# rj45_hub.net
KiCad netlist of a schematic drawn in Altium Designer
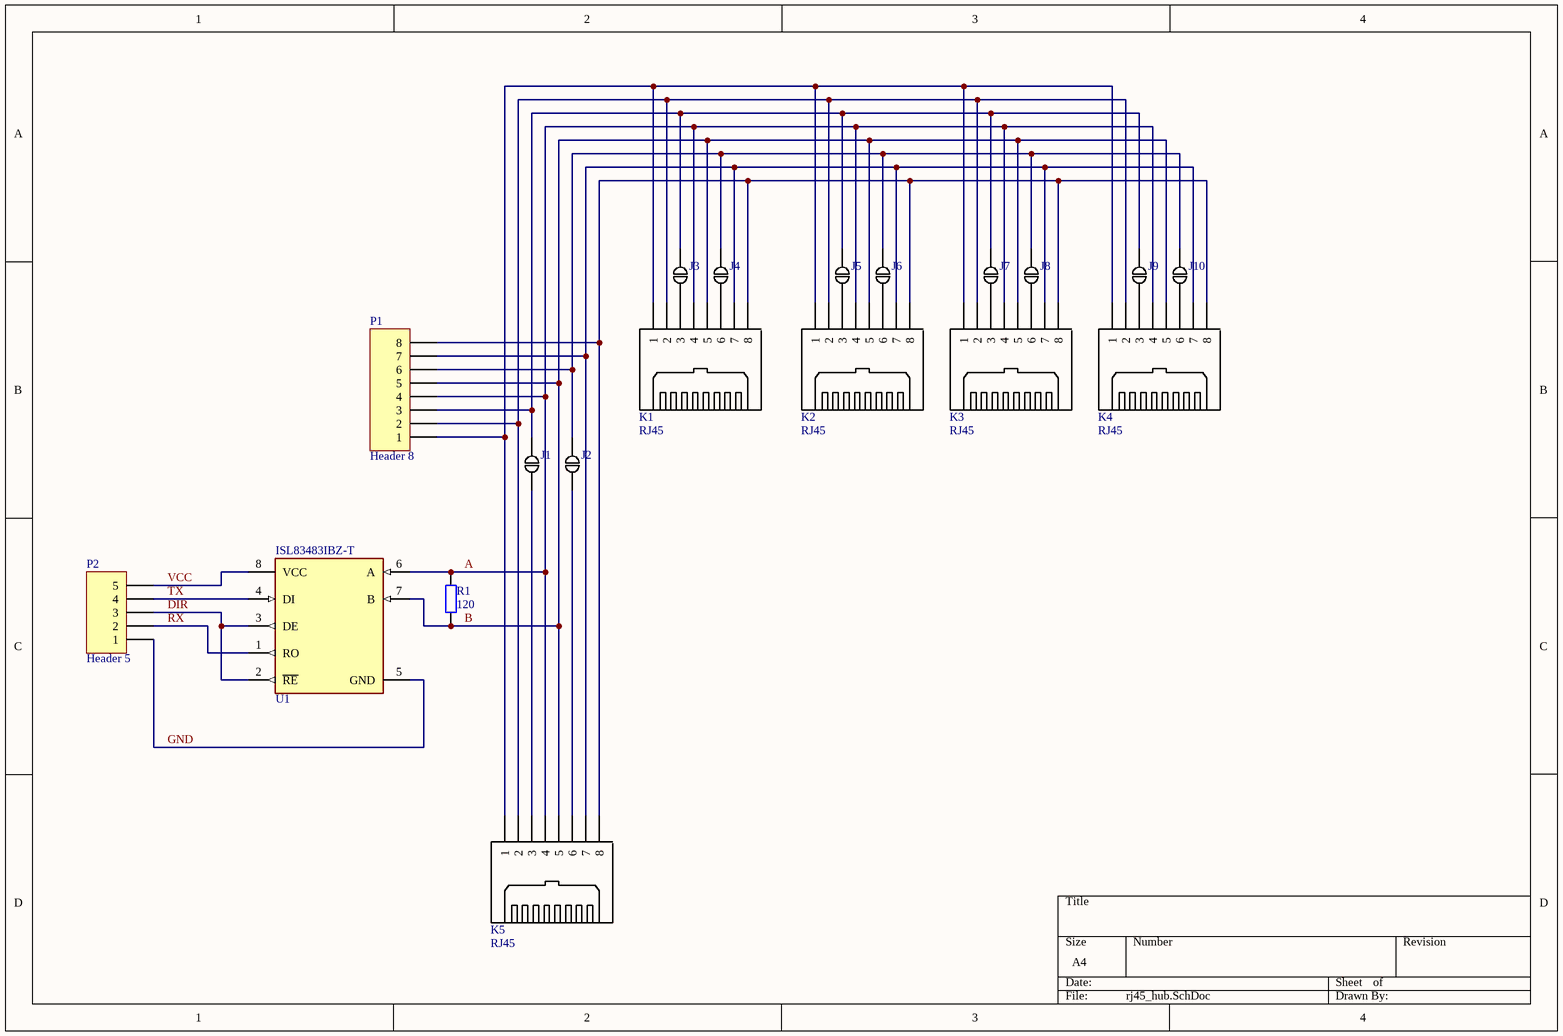
[diagram p0: rj45_hub.SchDoc]

(export (version "E")
  (design (tool "Eeschema 10.0.6"))
  (components
    (comp (ref "J1")
      (value "~")
      (footprint "SOLDER_JUMP")
      (description "SOLDERDOT BYPASS")
      (libsource (lib "vh_altium_library") (part "BYPASS-MINI"))
    )
    (comp (ref "J2")
      (value "~")
      (footprint "SOLDER_JUMP")
      (description "SOLDERDOT BYPASS")
      (libsource (lib "vh_altium_library") (part "BYPASS-MINI"))
    )
    (comp (ref "J3")
      (value "~")
      (footprint "SOLDER_JUMP")
      (description "SOLDERDOT BYPASS")
      (libsource (lib "vh_altium_library") (part "BYPASS-MINI"))
    )
    (comp (ref "J4")
      (value "~")
      (footprint "SOLDER_JUMP")
      (description "SOLDERDOT BYPASS")
      (libsource (lib "vh_altium_library") (part "BYPASS-MINI"))
    )
    (comp (ref "J5")
      (value "~")
      (footprint "SOLDER_JUMP")
      (description "SOLDERDOT BYPASS")
      (libsource (lib "vh_altium_library") (part "BYPASS-MINI"))
    )
    (comp (ref "J6")
      (value "~")
      (footprint "SOLDER_JUMP")
      (description "SOLDERDOT BYPASS")
      (libsource (lib "vh_altium_library") (part "BYPASS-MINI"))
    )
    (comp (ref "J7")
      (value "~")
      (footprint "SOLDER_JUMP")
      (description "SOLDERDOT BYPASS")
      (libsource (lib "vh_altium_library") (part "BYPASS-MINI"))
    )
    (comp (ref "J8")
      (value "~")
      (footprint "SOLDER_JUMP")
      (description "SOLDERDOT BYPASS")
      (libsource (lib "vh_altium_library") (part "BYPASS-MINI"))
    )
    (comp (ref "J9")
      (value "~")
      (footprint "SOLDER_JUMP")
      (description "SOLDERDOT BYPASS")
      (libsource (lib "vh_altium_library") (part "BYPASS-MINI"))
    )
    (comp (ref "J10")
      (value "~")
      (footprint "SOLDER_JUMP")
      (description "SOLDERDOT BYPASS")
      (libsource (lib "vh_altium_library") (part "BYPASS-MINI"))
    )
    (comp (ref "K1") (value "RJ45") (footprint "rj45") (libsource (lib "vh_altium_library") (part "RJ45")))
    (comp (ref "K2") (value "RJ45") (footprint "rj45") (libsource (lib "vh_altium_library") (part "RJ45")))
    (comp (ref "K3") (value "RJ45") (footprint "rj45") (libsource (lib "vh_altium_library") (part "RJ45")))
    (comp (ref "K4") (value "RJ45") (footprint "rj45") (libsource (lib "vh_altium_library") (part "RJ45")))
    (comp (ref "K5") (value "RJ45") (footprint "rj45") (libsource (lib "vh_altium_library") (part "RJ45")))
    (comp (ref "P1")
      (value "Header 8")
      (footprint "HDR1X8")
      (description "Header, 8-Pin")
      (fields (field (name "PUBLISHER") "Altium Limited"))
      (libsource (lib "Miscellaneous Connectors") (part "Header 8"))
    )
    (comp (ref "P2")
      (value "Header 5")
      (footprint "HDR1X5")
      (description "Header, 5-Pin")
      (fields (field (name "PUBLISHER") "Altium Limited"))
      (libsource (lib "Miscellaneous Connectors") (part "Header 5"))
    )
    (comp (ref "R1")
      (value "120")
      (footprint "0603R-GENERIC")
      (description "Resistor")
      (fields (field (name "Comment") "Res2") (field (name "PUBLISHER") "Altium Limited"))
      (libsource (lib "Miscellaneous Devices") (part "Res2"))
    )
    (comp (ref "U1")
      (value "ISL83483IBZ-T")
      (footprint "FP-S8-5-MFG")
      (description "IC TRANSCEIVER HALF 1/1 8SOIC")
      (fields
        (field (name "MANUFACTURER PART NUMBER") "MAX483ECSA+")
        (field (name "OCTOPART") "https://octopart.com/max483ecsa%2B-maxim+integrated-39583309")
      )
      (libsource (lib "Altium Content Vault") (part "CMP-05679-000034-1"))
    )
  )
  (nets
    (net (code "1") (name "/A") (class "Default")
      (node (ref "K1") (pin "4") (pinfunction "4_4") (pintype "passive"))
      (node (ref "K2") (pin "4") (pinfunction "4_4") (pintype "passive"))
      (node (ref "K3") (pin "4") (pinfunction "4_4") (pintype "passive"))
      (node (ref "K4") (pin "4") (pinfunction "4_4") (pintype "passive"))
      (node (ref "K5") (pin "4") (pinfunction "4_4") (pintype "passive"))
      (node (ref "P1") (pin "4") (pinfunction "4_4") (pintype "passive"))
      (node (ref "R1") (pin "2") (pinfunction "2_2") (pintype "passive"))
      (node (ref "U1") (pin "6") (pinfunction "A_6") (pintype "input"))
    )
    (net (code "2") (name "/B") (class "Default")
      (node (ref "K1") (pin "5") (pinfunction "5_5") (pintype "passive"))
      (node (ref "K2") (pin "5") (pinfunction "5_5") (pintype "passive"))
      (node (ref "K3") (pin "5") (pinfunction "5_5") (pintype "passive"))
      (node (ref "K4") (pin "5") (pinfunction "5_5") (pintype "passive"))
      (node (ref "K5") (pin "5") (pinfunction "5_5") (pintype "passive"))
      (node (ref "P1") (pin "5") (pinfunction "5_5") (pintype "passive"))
      (node (ref "R1") (pin "1") (pinfunction "1_1") (pintype "passive"))
      (node (ref "U1") (pin "7") (pinfunction "B_7") (pintype "input"))
    )
    (net (code "3") (name "/DIR") (class "Default")
      (node (ref "P2") (pin "3") (pinfunction "3_3") (pintype "passive"))
      (node (ref "U1") (pin "2") (pinfunction "~{RE}_2") (pintype "output"))
      (node (ref "U1") (pin "3") (pinfunction "DE_3") (pintype "output"))
    )
    (net (code "4") (name "/GND") (class "Default")
      (node (ref "P2") (pin "1") (pinfunction "1_1") (pintype "passive"))
      (node (ref "U1") (pin "5") (pinfunction "GND_5") (pintype "power_in"))
    )
    (net (code "5") (name "/RX") (class "Default")
      (node (ref "P2") (pin "2") (pinfunction "2_2") (pintype "passive"))
      (node (ref "U1") (pin "1") (pinfunction "RO_1") (pintype "output"))
    )
    (net (code "6") (name "/TX") (class "Default")
      (node (ref "P2") (pin "4") (pinfunction "4_4") (pintype "passive"))
      (node (ref "U1") (pin "4") (pinfunction "DI_4") (pintype "input"))
    )
    (net (code "7") (name "/VCC") (class "Default")
      (node (ref "P2") (pin "5") (pinfunction "5_5") (pintype "passive"))
      (node (ref "U1") (pin "8") (pinfunction "VCC_8") (pintype "power_in"))
    )
    (net (code "8") (name "Net-(J1-Pad1)") (class "Default")
      (node (ref "J1") (pin "1") (pinfunction "1_1") (pintype "passive"))
      (node (ref "J3") (pin "1") (pinfunction "1_1") (pintype "passive"))
      (node (ref "J5") (pin "1") (pinfunction "1_1") (pintype "passive"))
      (node (ref "J7") (pin "1") (pinfunction "1_1") (pintype "passive"))
      (node (ref "J9") (pin "1") (pinfunction "1_1") (pintype "passive"))
      (node (ref "P1") (pin "3") (pinfunction "3_3") (pintype "passive"))
    )
    (net (code "9") (name "Net-(J1-Pad2)") (class "Default")
      (node (ref "J1") (pin "2") (pinfunction "2_2") (pintype "passive"))
      (node (ref "K5") (pin "3") (pinfunction "3_3") (pintype "passive"))
    )
    (net (code "10") (name "Net-(J2-Pad2)") (class "Default")
      (node (ref "J2") (pin "2") (pinfunction "2_2") (pintype "passive"))
      (node (ref "K5") (pin "6") (pinfunction "6_6") (pintype "passive"))
    )
    (net (code "11") (name "Net-(J3-Pad2)") (class "Default")
      (node (ref "J3") (pin "2") (pinfunction "2_2") (pintype "passive"))
      (node (ref "K1") (pin "3") (pinfunction "3_3") (pintype "passive"))
    )
    (net (code "12") (name "Net-(J4-Pad2)") (class "Default")
      (node (ref "J4") (pin "2") (pinfunction "2_2") (pintype "passive"))
      (node (ref "K1") (pin "6") (pinfunction "6_6") (pintype "passive"))
    )
    (net (code "13") (name "Net-(J5-Pad2)") (class "Default")
      (node (ref "J5") (pin "2") (pinfunction "2_2") (pintype "passive"))
      (node (ref "K2") (pin "3") (pinfunction "3_3") (pintype "passive"))
    )
    (net (code "14") (name "Net-(J6-Pad2)") (class "Default")
      (node (ref "J6") (pin "2") (pinfunction "2_2") (pintype "passive"))
      (node (ref "K2") (pin "6") (pinfunction "6_6") (pintype "passive"))
    )
    (net (code "15") (name "Net-(J7-Pad2)") (class "Default")
      (node (ref "J7") (pin "2") (pinfunction "2_2") (pintype "passive"))
      (node (ref "K3") (pin "3") (pinfunction "3_3") (pintype "passive"))
    )
    (net (code "16") (name "Net-(J8-Pad2)") (class "Default")
      (node (ref "J8") (pin "2") (pinfunction "2_2") (pintype "passive"))
      (node (ref "K3") (pin "6") (pinfunction "6_6") (pintype "passive"))
    )
    (net (code "17") (name "Net-(J9-Pad2)") (class "Default")
      (node (ref "J9") (pin "2") (pinfunction "2_2") (pintype "passive"))
      (node (ref "K4") (pin "3") (pinfunction "3_3") (pintype "passive"))
    )
    (net (code "18") (name "Net-(J10-Pad1)") (class "Default")
      (node (ref "J10") (pin "1") (pinfunction "1_1") (pintype "passive"))
      (node (ref "J2") (pin "1") (pinfunction "1_1") (pintype "passive"))
      (node (ref "J4") (pin "1") (pinfunction "1_1") (pintype "passive"))
      (node (ref "J6") (pin "1") (pinfunction "1_1") (pintype "passive"))
      (node (ref "J8") (pin "1") (pinfunction "1_1") (pintype "passive"))
      (node (ref "P1") (pin "6") (pinfunction "6_6") (pintype "passive"))
    )
    (net (code "19") (name "Net-(J10-Pad2)") (class "Default")
      (node (ref "J10") (pin "2") (pinfunction "2_2") (pintype "passive"))
      (node (ref "K4") (pin "6") (pinfunction "6_6") (pintype "passive"))
    )
    (net (code "20") (name "Net-(K1-Pad1)") (class "Default")
      (node (ref "K1") (pin "1") (pinfunction "1_1") (pintype "passive"))
      (node (ref "K2") (pin "1") (pinfunction "1_1") (pintype "passive"))
      (node (ref "K3") (pin "1") (pinfunction "1_1") (pintype "passive"))
      (node (ref "K4") (pin "1") (pinfunction "1_1") (pintype "passive"))
      (node (ref "K5") (pin "1") (pinfunction "1_1") (pintype "passive"))
      (node (ref "P1") (pin "1") (pinfunction "1_1") (pintype "passive"))
    )
    (net (code "21") (name "Net-(K1-Pad2)") (class "Default")
      (node (ref "K1") (pin "2") (pinfunction "2_2") (pintype "passive"))
      (node (ref "K2") (pin "2") (pinfunction "2_2") (pintype "passive"))
      (node (ref "K3") (pin "2") (pinfunction "2_2") (pintype "passive"))
      (node (ref "K4") (pin "2") (pinfunction "2_2") (pintype "passive"))
      (node (ref "K5") (pin "2") (pinfunction "2_2") (pintype "passive"))
      (node (ref "P1") (pin "2") (pinfunction "2_2") (pintype "passive"))
    )
    (net (code "22") (name "Net-(K1-Pad7)") (class "Default")
      (node (ref "K1") (pin "7") (pinfunction "7_7") (pintype "passive"))
      (node (ref "K2") (pin "7") (pinfunction "7_7") (pintype "passive"))
      (node (ref "K3") (pin "7") (pinfunction "7_7") (pintype "passive"))
      (node (ref "K4") (pin "7") (pinfunction "7_7") (pintype "passive"))
      (node (ref "K5") (pin "7") (pinfunction "7_7") (pintype "passive"))
      (node (ref "P1") (pin "7") (pinfunction "7_7") (pintype "passive"))
    )
    (net (code "23") (name "Net-(K1-Pad8)") (class "Default")
      (node (ref "K1") (pin "8") (pinfunction "8_8") (pintype "passive"))
      (node (ref "K2") (pin "8") (pinfunction "8_8") (pintype "passive"))
      (node (ref "K3") (pin "8") (pinfunction "8_8") (pintype "passive"))
      (node (ref "K4") (pin "8") (pinfunction "8_8") (pintype "passive"))
      (node (ref "K5") (pin "8") (pinfunction "8_8") (pintype "passive"))
      (node (ref "P1") (pin "8") (pinfunction "8_8") (pintype "passive"))
    )
  )
)
